# iPhone11-2NEI.net
KiCad netlist of a schematic drawn in Altium Designer
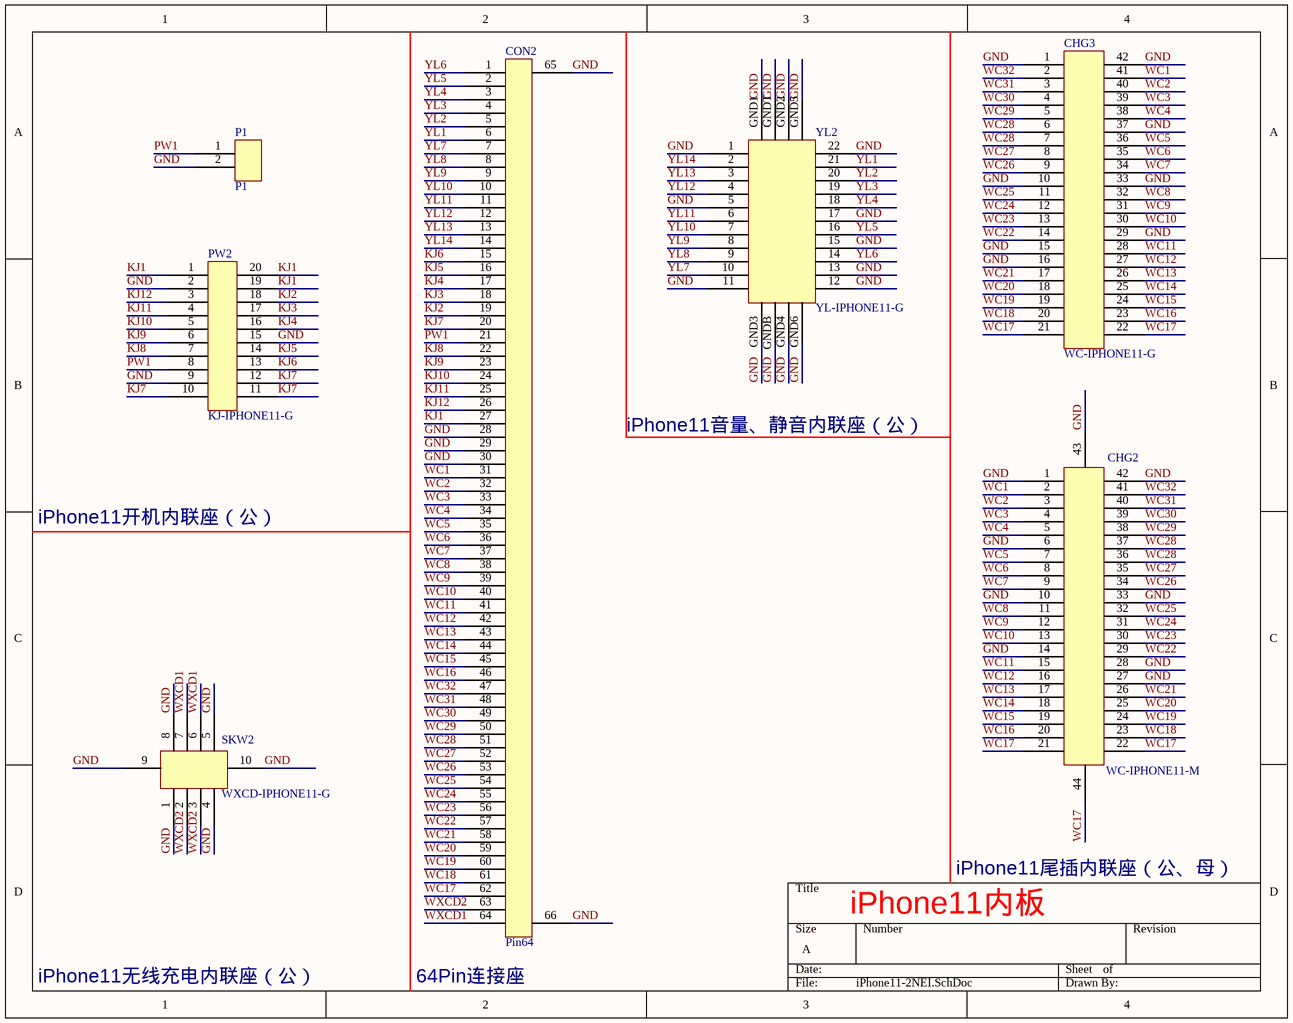
[diagram p0: iPhone11-2NEI.SchDoc]

(export (version "E")
  (design (tool "Eeschema 10.0.6"))
  (components
    (comp (ref "CHG2")
      (value "WC-IPHONE11-M")
      (footprint "IPHONE11-WC-M")
      (libsource (lib "iPhone") (part "WC-IPHONE11-M"))
    )
    (comp (ref "CHG3")
      (value "WC-IPHONE11-G")
      (footprint "IPHONE11-WC-G")
      (libsource (lib "iPhone") (part "WC-IPHONE11-G"))
    )
    (comp (ref "CON2") (value "Pin64") (footprint "Pin64") (libsource (lib "iPhone") (part "Pin64")))
    (comp (ref "P1") (value "P1") (footprint "P-2") (libsource (lib "iPhone") (part "P1")))
    (comp (ref "PW2")
      (value "KJ-IPHONE11-G")
      (footprint "IPHONE11-KJ-G")
      (libsource (lib "iPhone") (part "KJ-IPHONE11-G"))
    )
    (comp (ref "SKW2")
      (value "WXCD-IPHONE11-G")
      (footprint "IPHONE11-WXCD-G")
      (libsource (lib "iPhone") (part "WXCD-IPHONE11-G"))
    )
    (comp (ref "YL2")
      (value "YL-IPHONE11-G")
      (footprint "IPHONE11-YL-G")
      (libsource (lib "iPhone") (part "YL-IPHONE11-G"))
    )
  )
  (nets
    (net (code "1") (name "/GND") (class "Default")
      (node (ref "CHG2") (pin "1") (pintype "passive"))
      (node (ref "CHG2") (pin "10") (pintype "passive"))
      (node (ref "CHG2") (pin "14") (pintype "passive"))
      (node (ref "CHG2") (pin "27") (pintype "passive"))
      (node (ref "CHG2") (pin "28") (pintype "passive"))
      (node (ref "CHG2") (pin "33") (pintype "passive"))
      (node (ref "CHG2") (pin "42") (pintype "passive"))
      (node (ref "CHG2") (pin "43") (pintype "passive"))
      (node (ref "CHG2") (pin "6") (pintype "passive"))
      (node (ref "CHG3") (pin "1") (pintype "passive"))
      (node (ref "CHG3") (pin "10") (pintype "passive"))
      (node (ref "CHG3") (pin "15") (pintype "passive"))
      (node (ref "CHG3") (pin "16") (pintype "passive"))
      (node (ref "CHG3") (pin "29") (pintype "passive"))
      (node (ref "CHG3") (pin "33") (pintype "passive"))
      (node (ref "CHG3") (pin "37") (pintype "passive"))
      (node (ref "CHG3") (pin "42") (pintype "passive"))
      (node (ref "CON2") (pin "28") (pintype "passive"))
      (node (ref "CON2") (pin "29") (pintype "passive"))
      (node (ref "CON2") (pin "30") (pintype "passive"))
      (node (ref "CON2") (pin "65") (pintype "passive"))
      (node (ref "CON2") (pin "66") (pintype "passive"))
      (node (ref "P1") (pin "2") (pintype "passive"))
      (node (ref "PW2") (pin "15") (pintype "passive"))
      (node (ref "PW2") (pin "2") (pintype "passive"))
      (node (ref "PW2") (pin "9") (pintype "passive"))
      (node (ref "SKW2") (pin "1") (pintype "passive"))
      (node (ref "SKW2") (pin "10") (pintype "passive"))
      (node (ref "SKW2") (pin "4") (pintype "passive"))
      (node (ref "SKW2") (pin "5") (pintype "passive"))
      (node (ref "SKW2") (pin "8") (pintype "passive"))
      (node (ref "SKW2") (pin "9") (pintype "passive"))
      (node (ref "YL2") (pin "1") (pintype "passive"))
      (node (ref "YL2") (pin "11") (pintype "passive"))
      (node (ref "YL2") (pin "12") (pintype "passive"))
      (node (ref "YL2") (pin "13") (pintype "passive"))
      (node (ref "YL2") (pin "15") (pintype "passive"))
      (node (ref "YL2") (pin "17") (pintype "passive"))
      (node (ref "YL2") (pin "22") (pintype "passive"))
      (node (ref "YL2") (pin "5") (pintype "passive"))
      (node (ref "YL2") (pin "GND1") (pintype "passive"))
      (node (ref "YL2") (pin "GND2") (pintype "passive"))
      (node (ref "YL2") (pin "GND3") (pintype "passive"))
      (node (ref "YL2") (pin "GND4") (pintype "passive"))
      (node (ref "YL2") (pin "GND5") (pintype "passive"))
      (node (ref "YL2") (pin "GND6") (pintype "passive"))
      (node (ref "YL2") (pin "GNDB") (pintype "passive"))
      (node (ref "YL2") (pin "GNDT") (pintype "passive"))
    )
    (net (code "2") (name "/KJ1") (class "Default")
      (node (ref "CON2") (pin "27") (pintype "passive"))
      (node (ref "PW2") (pin "1") (pintype "passive"))
      (node (ref "PW2") (pin "19") (pintype "passive"))
      (node (ref "PW2") (pin "20") (pintype "passive"))
    )
    (net (code "3") (name "/KJ2") (class "Default")
      (node (ref "CON2") (pin "19") (pintype "passive"))
      (node (ref "PW2") (pin "18") (pintype "passive"))
    )
    (net (code "4") (name "/KJ3") (class "Default")
      (node (ref "CON2") (pin "18") (pintype "passive"))
      (node (ref "PW2") (pin "17") (pintype "passive"))
    )
    (net (code "5") (name "/KJ4") (class "Default")
      (node (ref "CON2") (pin "17") (pintype "passive"))
      (node (ref "PW2") (pin "16") (pintype "passive"))
    )
    (net (code "6") (name "/KJ5") (class "Default")
      (node (ref "CON2") (pin "16") (pintype "passive"))
      (node (ref "PW2") (pin "14") (pintype "passive"))
    )
    (net (code "7") (name "/KJ6") (class "Default")
      (node (ref "CON2") (pin "15") (pintype "passive"))
      (node (ref "PW2") (pin "13") (pintype "passive"))
    )
    (net (code "8") (name "/KJ7") (class "Default")
      (node (ref "CON2") (pin "20") (pintype "passive"))
      (node (ref "PW2") (pin "10") (pintype "passive"))
      (node (ref "PW2") (pin "11") (pintype "passive"))
      (node (ref "PW2") (pin "12") (pintype "passive"))
    )
    (net (code "9") (name "/KJ8") (class "Default")
      (node (ref "CON2") (pin "22") (pintype "passive"))
      (node (ref "PW2") (pin "7") (pintype "passive"))
    )
    (net (code "10") (name "/KJ9") (class "Default")
      (node (ref "CON2") (pin "23") (pintype "passive"))
      (node (ref "PW2") (pin "6") (pintype "passive"))
    )
    (net (code "11") (name "/KJ10") (class "Default")
      (node (ref "CON2") (pin "24") (pintype "passive"))
      (node (ref "PW2") (pin "5") (pintype "passive"))
    )
    (net (code "12") (name "/KJ11") (class "Default")
      (node (ref "CON2") (pin "25") (pintype "passive"))
      (node (ref "PW2") (pin "4") (pintype "passive"))
    )
    (net (code "13") (name "/KJ12") (class "Default")
      (node (ref "CON2") (pin "26") (pintype "passive"))
      (node (ref "PW2") (pin "3") (pintype "passive"))
    )
    (net (code "14") (name "/PW1") (class "Default")
      (node (ref "CON2") (pin "21") (pintype "passive"))
      (node (ref "P1") (pin "1") (pintype "passive"))
      (node (ref "PW2") (pin "8") (pintype "passive"))
    )
    (net (code "15") (name "/WC1") (class "Default")
      (node (ref "CHG2") (pin "2") (pintype "passive"))
      (node (ref "CHG3") (pin "41") (pintype "passive"))
      (node (ref "CON2") (pin "31") (pintype "passive"))
    )
    (net (code "16") (name "/WC2") (class "Default")
      (node (ref "CHG2") (pin "3") (pintype "passive"))
      (node (ref "CHG3") (pin "40") (pintype "passive"))
      (node (ref "CON2") (pin "32") (pintype "passive"))
    )
    (net (code "17") (name "/WC3") (class "Default")
      (node (ref "CHG2") (pin "4") (pintype "passive"))
      (node (ref "CHG3") (pin "39") (pintype "passive"))
      (node (ref "CON2") (pin "33") (pintype "passive"))
    )
    (net (code "18") (name "/WC4") (class "Default")
      (node (ref "CHG2") (pin "5") (pintype "passive"))
      (node (ref "CHG3") (pin "38") (pintype "passive"))
      (node (ref "CON2") (pin "34") (pintype "passive"))
    )
    (net (code "19") (name "/WC5") (class "Default")
      (node (ref "CHG2") (pin "7") (pintype "passive"))
      (node (ref "CHG3") (pin "36") (pintype "passive"))
      (node (ref "CON2") (pin "35") (pintype "passive"))
    )
    (net (code "20") (name "/WC6") (class "Default")
      (node (ref "CHG2") (pin "8") (pintype "passive"))
      (node (ref "CHG3") (pin "35") (pintype "passive"))
      (node (ref "CON2") (pin "36") (pintype "passive"))
    )
    (net (code "21") (name "/WC7") (class "Default")
      (node (ref "CHG2") (pin "9") (pintype "passive"))
      (node (ref "CHG3") (pin "34") (pintype "passive"))
      (node (ref "CON2") (pin "37") (pintype "passive"))
    )
    (net (code "22") (name "/WC8") (class "Default")
      (node (ref "CHG2") (pin "11") (pintype "passive"))
      (node (ref "CHG3") (pin "32") (pintype "passive"))
      (node (ref "CON2") (pin "38") (pintype "passive"))
    )
    (net (code "23") (name "/WC9") (class "Default")
      (node (ref "CHG2") (pin "12") (pintype "passive"))
      (node (ref "CHG3") (pin "31") (pintype "passive"))
      (node (ref "CON2") (pin "39") (pintype "passive"))
    )
    (net (code "24") (name "/WC10") (class "Default")
      (node (ref "CHG2") (pin "13") (pintype "passive"))
      (node (ref "CHG3") (pin "30") (pintype "passive"))
      (node (ref "CON2") (pin "40") (pintype "passive"))
    )
    (net (code "25") (name "/WC11") (class "Default")
      (node (ref "CHG2") (pin "15") (pintype "passive"))
      (node (ref "CHG3") (pin "28") (pintype "passive"))
      (node (ref "CON2") (pin "41") (pintype "passive"))
    )
    (net (code "26") (name "/WC12") (class "Default")
      (node (ref "CHG2") (pin "16") (pintype "passive"))
      (node (ref "CHG3") (pin "27") (pintype "passive"))
      (node (ref "CON2") (pin "42") (pintype "passive"))
    )
    (net (code "27") (name "/WC13") (class "Default")
      (node (ref "CHG2") (pin "17") (pintype "passive"))
      (node (ref "CHG3") (pin "26") (pintype "passive"))
      (node (ref "CON2") (pin "43") (pintype "passive"))
    )
    (net (code "28") (name "/WC14") (class "Default")
      (node (ref "CHG2") (pin "18") (pintype "passive"))
      (node (ref "CHG3") (pin "25") (pintype "passive"))
      (node (ref "CON2") (pin "44") (pintype "passive"))
    )
    (net (code "29") (name "/WC15") (class "Default")
      (node (ref "CHG2") (pin "19") (pintype "passive"))
      (node (ref "CHG3") (pin "24") (pintype "passive"))
      (node (ref "CON2") (pin "45") (pintype "passive"))
    )
    (net (code "30") (name "/WC16") (class "Default")
      (node (ref "CHG2") (pin "20") (pintype "passive"))
      (node (ref "CHG3") (pin "23") (pintype "passive"))
      (node (ref "CON2") (pin "46") (pintype "passive"))
    )
    (net (code "31") (name "/WC17") (class "Default")
      (node (ref "CHG2") (pin "21") (pintype "passive"))
      (node (ref "CHG2") (pin "22") (pintype "passive"))
      (node (ref "CHG2") (pin "44") (pintype "passive"))
      (node (ref "CHG3") (pin "21") (pintype "passive"))
      (node (ref "CHG3") (pin "22") (pintype "passive"))
      (node (ref "CON2") (pin "62") (pintype "passive"))
    )
    (net (code "32") (name "/WC18") (class "Default")
      (node (ref "CHG2") (pin "23") (pintype "passive"))
      (node (ref "CHG3") (pin "20") (pintype "passive"))
      (node (ref "CON2") (pin "61") (pintype "passive"))
    )
    (net (code "33") (name "/WC19") (class "Default")
      (node (ref "CHG2") (pin "24") (pintype "passive"))
      (node (ref "CHG3") (pin "19") (pintype "passive"))
      (node (ref "CON2") (pin "60") (pintype "passive"))
    )
    (net (code "34") (name "/WC20") (class "Default")
      (node (ref "CHG2") (pin "25") (pintype "passive"))
      (node (ref "CHG3") (pin "18") (pintype "passive"))
      (node (ref "CON2") (pin "59") (pintype "passive"))
    )
    (net (code "35") (name "/WC21") (class "Default")
      (node (ref "CHG2") (pin "26") (pintype "passive"))
      (node (ref "CHG3") (pin "17") (pintype "passive"))
      (node (ref "CON2") (pin "58") (pintype "passive"))
    )
    (net (code "36") (name "/WC22") (class "Default")
      (node (ref "CHG2") (pin "29") (pintype "passive"))
      (node (ref "CHG3") (pin "14") (pintype "passive"))
      (node (ref "CON2") (pin "57") (pintype "passive"))
    )
    (net (code "37") (name "/WC23") (class "Default")
      (node (ref "CHG2") (pin "30") (pintype "passive"))
      (node (ref "CHG3") (pin "13") (pintype "passive"))
      (node (ref "CON2") (pin "56") (pintype "passive"))
    )
    (net (code "38") (name "/WC24") (class "Default")
      (node (ref "CHG2") (pin "31") (pintype "passive"))
      (node (ref "CHG3") (pin "12") (pintype "passive"))
      (node (ref "CON2") (pin "55") (pintype "passive"))
    )
    (net (code "39") (name "/WC25") (class "Default")
      (node (ref "CHG2") (pin "32") (pintype "passive"))
      (node (ref "CHG3") (pin "11") (pintype "passive"))
      (node (ref "CON2") (pin "54") (pintype "passive"))
    )
    (net (code "40") (name "/WC26") (class "Default")
      (node (ref "CHG2") (pin "34") (pintype "passive"))
      (node (ref "CHG3") (pin "9") (pintype "passive"))
      (node (ref "CON2") (pin "53") (pintype "passive"))
    )
    (net (code "41") (name "/WC27") (class "Default")
      (node (ref "CHG2") (pin "35") (pintype "passive"))
      (node (ref "CHG3") (pin "8") (pintype "passive"))
      (node (ref "CON2") (pin "52") (pintype "passive"))
    )
    (net (code "42") (name "/WC28") (class "Default")
      (node (ref "CHG2") (pin "36") (pintype "passive"))
      (node (ref "CHG2") (pin "37") (pintype "passive"))
      (node (ref "CHG3") (pin "6") (pintype "passive"))
      (node (ref "CHG3") (pin "7") (pintype "passive"))
      (node (ref "CON2") (pin "51") (pintype "passive"))
    )
    (net (code "43") (name "/WC29") (class "Default")
      (node (ref "CHG2") (pin "38") (pintype "passive"))
      (node (ref "CHG3") (pin "5") (pintype "passive"))
      (node (ref "CON2") (pin "50") (pintype "passive"))
    )
    (net (code "44") (name "/WC30") (class "Default")
      (node (ref "CHG2") (pin "39") (pintype "passive"))
      (node (ref "CHG3") (pin "4") (pintype "passive"))
      (node (ref "CON2") (pin "49") (pintype "passive"))
    )
    (net (code "45") (name "/WC31") (class "Default")
      (node (ref "CHG2") (pin "40") (pintype "passive"))
      (node (ref "CHG3") (pin "3") (pintype "passive"))
      (node (ref "CON2") (pin "48") (pintype "passive"))
    )
    (net (code "46") (name "/WC32") (class "Default")
      (node (ref "CHG2") (pin "41") (pintype "passive"))
      (node (ref "CHG3") (pin "2") (pintype "passive"))
      (node (ref "CON2") (pin "47") (pintype "passive"))
    )
    (net (code "47") (name "/WXCD1") (class "Default")
      (node (ref "CON2") (pin "64") (pintype "passive"))
      (node (ref "SKW2") (pin "6") (pintype "passive"))
      (node (ref "SKW2") (pin "7") (pintype "passive"))
    )
    (net (code "48") (name "/WXCD2") (class "Default")
      (node (ref "CON2") (pin "63") (pintype "passive"))
      (node (ref "SKW2") (pin "2") (pintype "passive"))
      (node (ref "SKW2") (pin "3") (pintype "passive"))
    )
    (net (code "49") (name "/YL1") (class "Default")
      (node (ref "CON2") (pin "6") (pintype "passive"))
      (node (ref "YL2") (pin "21") (pintype "passive"))
    )
    (net (code "50") (name "/YL2") (class "Default")
      (node (ref "CON2") (pin "5") (pintype "passive"))
      (node (ref "YL2") (pin "20") (pintype "passive"))
    )
    (net (code "51") (name "/YL3") (class "Default")
      (node (ref "CON2") (pin "4") (pintype "passive"))
      (node (ref "YL2") (pin "19") (pintype "passive"))
    )
    (net (code "52") (name "/YL4") (class "Default")
      (node (ref "CON2") (pin "3") (pintype "passive"))
      (node (ref "YL2") (pin "18") (pintype "passive"))
    )
    (net (code "53") (name "/YL5") (class "Default")
      (node (ref "CON2") (pin "2") (pintype "passive"))
      (node (ref "YL2") (pin "16") (pintype "passive"))
    )
    (net (code "54") (name "/YL6") (class "Default")
      (node (ref "CON2") (pin "1") (pintype "passive"))
      (node (ref "YL2") (pin "14") (pintype "passive"))
    )
    (net (code "55") (name "/YL7") (class "Default")
      (node (ref "CON2") (pin "7") (pintype "passive"))
      (node (ref "YL2") (pin "10") (pintype "passive"))
    )
    (net (code "56") (name "/YL8") (class "Default")
      (node (ref "CON2") (pin "8") (pintype "passive"))
      (node (ref "YL2") (pin "9") (pintype "passive"))
    )
    (net (code "57") (name "/YL9") (class "Default")
      (node (ref "CON2") (pin "9") (pintype "passive"))
      (node (ref "YL2") (pin "8") (pintype "passive"))
    )
    (net (code "58") (name "/YL10") (class "Default")
      (node (ref "CON2") (pin "10") (pintype "passive"))
      (node (ref "YL2") (pin "7") (pintype "passive"))
    )
    (net (code "59") (name "/YL11") (class "Default")
      (node (ref "CON2") (pin "11") (pintype "passive"))
      (node (ref "YL2") (pin "6") (pintype "passive"))
    )
    (net (code "60") (name "/YL12") (class "Default")
      (node (ref "CON2") (pin "12") (pintype "passive"))
      (node (ref "YL2") (pin "4") (pintype "passive"))
    )
    (net (code "61") (name "/YL13") (class "Default")
      (node (ref "CON2") (pin "13") (pintype "passive"))
      (node (ref "YL2") (pin "3") (pintype "passive"))
    )
    (net (code "62") (name "/YL14") (class "Default")
      (node (ref "CON2") (pin "14") (pintype "passive"))
      (node (ref "YL2") (pin "2") (pintype "passive"))
    )
  )
)
